# Heartrate_Monitor_Internal.net
KiCad netlist of a schematic drawn in Altium Designer
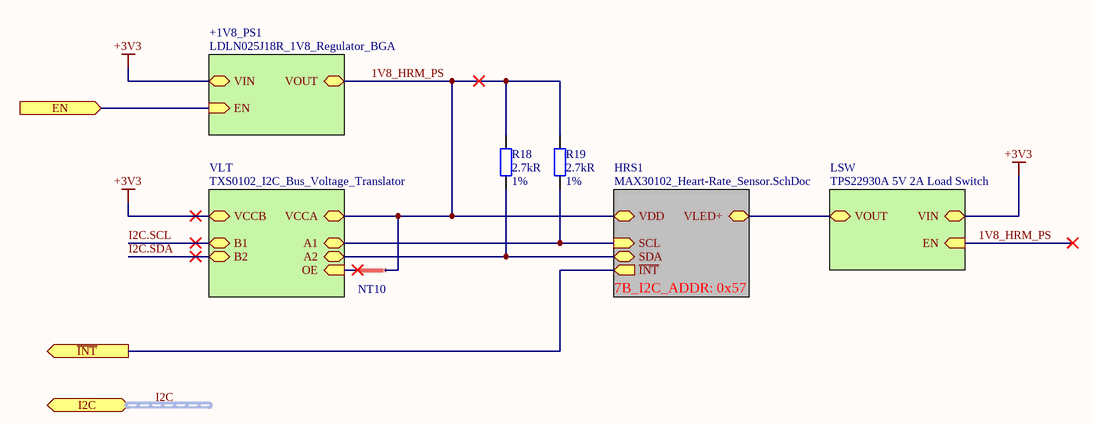
[diagram p0: Heartrate_Monitor_Internal.SchDoc]

(export (version "E")
  (design (tool "Eeschema 10.0.6"))
  (components
    (comp (ref "NT10")
      (value "Net Tie")
      (footprint "Net Tie 6x30mil")
      (libsource (lib "BLDC_Motor_Driver") (part "Net Tie Line"))
    )
    (comp (ref "R18")
      (value "RES SMD 2.7K OHM 1% 1/16W 0402")
      (footprint "R0402")
      (description "2.7 kOhms ±1% 0.063W, 1/16W Chip Resistor 0402 (1005 Metric) Moisture Resistant Thick Film")
      (fields
        (field (name "MANUFACTURER PART NUMBER") "RC0402FR-072K7L")
        (field (name "MANUFACTURER") "Yageo")
        (field (name "RESISTANCE") "2.7kR")
        (field (name "TOLERANCE") "1%")
      )
      (libsource (lib "resistors_smd") (part "RES SMD 2.7K OHM 1% 1/16W 0402"))
    )
    (comp (ref "R19")
      (value "RES SMD 2.7K OHM 1% 1/16W 0402")
      (footprint "R0402")
      (description "2.7 kOhms ±1% 0.063W, 1/16W Chip Resistor 0402 (1005 Metric) Moisture Resistant Thick Film")
      (fields
        (field (name "MANUFACTURER PART NUMBER") "RC0402FR-072K7L")
        (field (name "MANUFACTURER") "Yageo")
        (field (name "RESISTANCE") "2.7kR")
        (field (name "TOLERANCE") "1%")
      )
      (libsource (lib "resistors_smd") (part "RES SMD 2.7K OHM 1% 1/16W 0402"))
    )
  )
  (nets
    (net (code "3") (name "/1V8_HRM_PS") (class "Default")
      (node (ref "NT10") (pin "2") (pintype "passive"))
      (node (ref "R18") (pin "2") (pinfunction "2_2") (pintype "passive"))
      (node (ref "R19") (pin "2") (pinfunction "2_2") (pintype "passive"))
    )
    (net (code "4") (name "/A1") (class "Default")
      (node (ref "R19") (pin "1") (pinfunction "1_1") (pintype "passive"))
    )
    (net (code "5") (name "/A2") (class "Default")
      (node (ref "R18") (pin "1") (pinfunction "1_1") (pintype "passive"))
    )
    (net (code "10") (name "/OE") (class "Default")
      (node (ref "NT10") (pin "1") (pintype "passive+no_connect"))
    )
  )
)
